# PIC16F887.net
KiCad netlist of a schematic drawn in Altium Designer
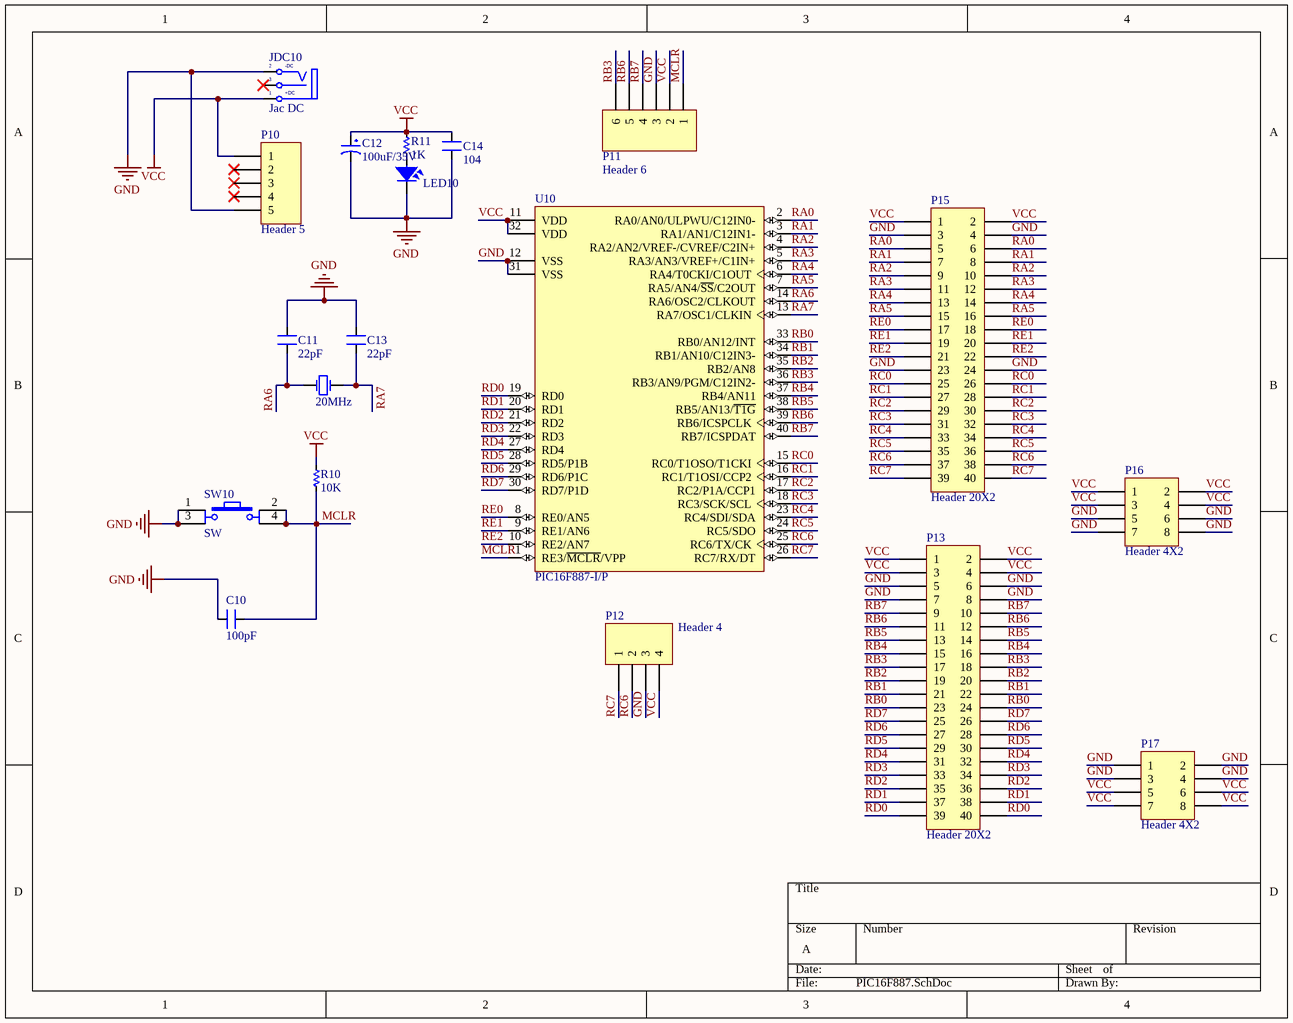
[diagram p0: PIC16F887.SchDoc]

(export (version "E")
  (design (tool "Eeschema 10.0.6"))
  (components
    (comp (ref "C10")
      (value "100pF")
      (footprint "CN1")
      (description "Cap np  1pF - 472pF")
      (libsource (lib "My Library") (part "CN1"))
    )
    (comp (ref "C11")
      (value "22pF")
      (footprint "CN1")
      (description "Cap np  1pF - 472pF")
      (libsource (lib "My Library") (part "CN1"))
    )
    (comp (ref "C12")
      (value "100uF/35V")
      (footprint "CP1.5/3.4")
      (description "Cap 100uF/35V - 470uF/16V")
      (libsource (lib "My Library") (part "CP3"))
    )
    (comp (ref "C13")
      (value "22pF")
      (footprint "CN1")
      (description "Cap np  1pF - 472pF")
      (libsource (lib "My Library") (part "CN1"))
    )
    (comp (ref "C14")
      (value "104")
      (footprint "CN1.5")
      (description "Cap np 682pF => 104pF")
      (libsource (lib "My Library") (part "CN1.5"))
    )
    (comp (ref "JDC10")
      (value "Jac DC")
      (footprint "DC-IN")
      (description "Jac DC input")
      (libsource (lib "My Library") (part "DCIN"))
    )
    (comp (ref "LED10")
      (value "LED")
      (footprint "LED-1206-Blue")
      (libsource (lib "My Library") (part "LED SMD"))
    )
    (comp (ref "P10")
      (value "Header 5")
      (footprint "HDR1X5")
      (description "Header, 5-Pin")
      (fields (field (name "PUBLISHER") "Altium Limited"))
      (libsource (lib "Miscellaneous Connectors") (part "Header 5"))
    )
    (comp (ref "P11")
      (value "Header 6")
      (footprint "HDR1X6")
      (description "Header, 6-Pin")
      (fields (field (name "PUBLISHER") "Altium Limited"))
      (libsource (lib "Miscellaneous Connectors") (part "Header 6"))
    )
    (comp (ref "P12")
      (value "Header 4")
      (footprint "HDR1X4")
      (description "Header, 4-Pin")
      (fields (field (name "PUBLISHER") "Altium Limited"))
      (libsource (lib "Miscellaneous Connectors") (part "Header 4"))
    )
    (comp (ref "P13")
      (value "Header 20X2")
      (footprint "HDR2X20")
      (description "Header, 20-Pin, Dual row")
      (fields (field (name "PUBLISHER") "Altium Limited"))
      (libsource (lib "Miscellaneous Connectors") (part "Header 20X2"))
    )
    (comp (ref "P15")
      (value "Header 20X2")
      (footprint "HDR2X20")
      (description "Header, 20-Pin, Dual row")
      (fields (field (name "PUBLISHER") "Altium Limited"))
      (libsource (lib "Miscellaneous Connectors") (part "Header 20X2"))
    )
    (comp (ref "P16")
      (value "Header 4X2")
      (footprint "HDR2X4")
      (description "Header, 4-Pin, Dual row")
      (fields (field (name "PUBLISHER") "Altium Limited"))
      (libsource (lib "Miscellaneous Connectors") (part "Header 4X2"))
    )
    (comp (ref "P17")
      (value "Header 4X2")
      (footprint "HDR2X4")
      (description "Header, 4-Pin, Dual row")
      (fields (field (name "PUBLISHER") "Altium Limited"))
      (libsource (lib "Miscellaneous Connectors") (part "Header 4X2"))
    )
    (comp (ref "R10")
      (value "10K")
      (footprint "RES-SMD-1206")
      (description "Resistor")
      (fields
        (field (name "MANUFACTURER") "Generic Components")
        (field (name "PUBLISHER") "Altium Hobart Technology Centre")
      )
      (libsource (lib "My Library") (part "Res-SMD"))
    )
    (comp (ref "R11")
      (value "1K")
      (footprint "RES-SMD-1206")
      (description "Resistor")
      (fields
        (field (name "MANUFACTURER") "Generic Components")
        (field (name "PUBLISHER") "Altium Hobart Technology Centre")
      )
      (libsource (lib "My Library") (part "Res-SMD"))
    )
    (comp (ref "SW10")
      (value "SW")
      (footprint "SW4")
      (description "Switch button 4 pin")
      (libsource (lib "My Library") (part "SW4"))
    )
    (comp (ref "U10")
      (value "PIC16F887-I/P")
      (footprint "PDIP600-P40")
      (fields (field (name "PUBLISHER") "Altium Limited"))
      (libsource (lib "Microchip Microcontroller 8-Bit PIC16") (part "PIC16F887-I/P"))
    )
    (comp (ref "Y10")
      (value "20MHz")
      (footprint "XTAL")
      (description "Crystal Oscillator")
      (fields (field (name "PUBLISHER") "Altium Limited"))
      (libsource (lib "My Library") (part "XTAL"))
    )
  )
  (nets
    (net (code "1") (name "/MCLR") (class "Default")
      (node (ref "C10") (pin "1") (pinfunction "1_1") (pintype "passive"))
      (node (ref "P11") (pin "1") (pinfunction "1_1") (pintype "passive"))
      (node (ref "R10") (pin "2") (pinfunction "2_2") (pintype "passive"))
      (node (ref "SW10") (pin "2") (pintype "passive"))
      (node (ref "SW10") (pin "4") (pintype "passive"))
      (node (ref "U10") (pin "1") (pinfunction "RE3/~{MCLR}/VPP_1") (pintype "bidirectional"))
    )
    (net (code "2") (name "/RA0") (class "Default")
      (node (ref "P15") (pin "5") (pinfunction "5_5") (pintype "passive"))
      (node (ref "P15") (pin "6") (pinfunction "6_6") (pintype "passive"))
      (node (ref "U10") (pin "2") (pinfunction "RA0/AN0/ULPWU/C12IN0-_2") (pintype "bidirectional"))
    )
    (net (code "3") (name "/RA1") (class "Default")
      (node (ref "P15") (pin "7") (pinfunction "7_7") (pintype "passive"))
      (node (ref "P15") (pin "8") (pinfunction "8_8") (pintype "passive"))
      (node (ref "U10") (pin "3") (pinfunction "RA1/AN1/C12IN1-_3") (pintype "bidirectional"))
    )
    (net (code "4") (name "/RA2") (class "Default")
      (node (ref "P15") (pin "10") (pinfunction "10_10") (pintype "passive"))
      (node (ref "P15") (pin "9") (pinfunction "9_9") (pintype "passive"))
      (node (ref "U10") (pin "4") (pinfunction "RA2/AN2/VREF-/CVREF/C2IN+_4") (pintype "bidirectional"))
    )
    (net (code "5") (name "/RA3") (class "Default")
      (node (ref "P15") (pin "11") (pinfunction "11_11") (pintype "passive"))
      (node (ref "P15") (pin "12") (pinfunction "12_12") (pintype "passive"))
      (node (ref "U10") (pin "5") (pinfunction "RA3/AN3/VREF+/C1IN+_5") (pintype "bidirectional"))
    )
    (net (code "6") (name "/RA4") (class "Default")
      (node (ref "P15") (pin "13") (pinfunction "13_13") (pintype "passive"))
      (node (ref "P15") (pin "14") (pinfunction "14_14") (pintype "passive"))
      (node (ref "U10") (pin "6") (pinfunction "RA4/T0CKI/C1OUT_6") (pintype "bidirectional"))
    )
    (net (code "7") (name "/RA5") (class "Default")
      (node (ref "P15") (pin "15") (pinfunction "15_15") (pintype "passive"))
      (node (ref "P15") (pin "16") (pinfunction "16_16") (pintype "passive"))
      (node (ref "U10") (pin "7") (pinfunction "RA5/AN4/~{SS}/C2OUT_7") (pintype "bidirectional"))
    )
    (net (code "8") (name "/RA6") (class "Default")
      (node (ref "C11") (pin "1") (pinfunction "1_1") (pintype "passive"))
      (node (ref "U10") (pin "14") (pinfunction "RA6/OSC2/CLKOUT_14") (pintype "bidirectional"))
      (node (ref "Y10") (pin "1") (pinfunction "OSC1_1") (pintype "passive"))
    )
    (net (code "9") (name "/RA7") (class "Default")
      (node (ref "C13") (pin "1") (pinfunction "1_1") (pintype "passive"))
      (node (ref "U10") (pin "13") (pinfunction "RA7/OSC1/CLKIN_13") (pintype "bidirectional"))
      (node (ref "Y10") (pin "2") (pinfunction "OSC2_2") (pintype "passive"))
    )
    (net (code "10") (name "/RB0") (class "Default")
      (node (ref "P13") (pin "23") (pinfunction "23_23") (pintype "passive"))
      (node (ref "P13") (pin "24") (pinfunction "24_24") (pintype "passive"))
      (node (ref "U10") (pin "33") (pinfunction "RB0/AN12/INT_33") (pintype "bidirectional"))
    )
    (net (code "11") (name "/RB1") (class "Default")
      (node (ref "P13") (pin "21") (pinfunction "21_21") (pintype "passive"))
      (node (ref "P13") (pin "22") (pinfunction "22_22") (pintype "passive"))
      (node (ref "U10") (pin "34") (pinfunction "RB1/AN10/C12IN3-_34") (pintype "bidirectional"))
    )
    (net (code "12") (name "/RB2") (class "Default")
      (node (ref "P13") (pin "19") (pinfunction "19_19") (pintype "passive"))
      (node (ref "P13") (pin "20") (pinfunction "20_20") (pintype "passive"))
      (node (ref "U10") (pin "35") (pinfunction "RB2/AN8_35") (pintype "bidirectional"))
    )
    (net (code "13") (name "/RB3") (class "Default")
      (node (ref "P11") (pin "6") (pinfunction "6_6") (pintype "passive"))
      (node (ref "P13") (pin "17") (pinfunction "17_17") (pintype "passive"))
      (node (ref "P13") (pin "18") (pinfunction "18_18") (pintype "passive"))
      (node (ref "U10") (pin "36") (pinfunction "RB3/AN9/PGM/C12IN2-_36") (pintype "bidirectional"))
    )
    (net (code "14") (name "/RB4") (class "Default")
      (node (ref "P13") (pin "15") (pinfunction "15_15") (pintype "passive"))
      (node (ref "P13") (pin "16") (pinfunction "16_16") (pintype "passive"))
      (node (ref "U10") (pin "37") (pinfunction "RB4/AN11_37") (pintype "bidirectional"))
    )
    (net (code "15") (name "/RB5") (class "Default")
      (node (ref "P13") (pin "13") (pinfunction "13_13") (pintype "passive"))
      (node (ref "P13") (pin "14") (pinfunction "14_14") (pintype "passive"))
      (node (ref "U10") (pin "38") (pinfunction "RB5/AN13/~{T1G}_38") (pintype "bidirectional"))
    )
    (net (code "16") (name "/RB6") (class "Default")
      (node (ref "P11") (pin "5") (pinfunction "5_5") (pintype "passive"))
      (node (ref "P13") (pin "11") (pinfunction "11_11") (pintype "passive"))
      (node (ref "P13") (pin "12") (pinfunction "12_12") (pintype "passive"))
      (node (ref "U10") (pin "39") (pinfunction "RB6/ICSPCLK_39") (pintype "bidirectional"))
    )
    (net (code "17") (name "/RB7") (class "Default")
      (node (ref "P11") (pin "4") (pinfunction "4_4") (pintype "passive"))
      (node (ref "P13") (pin "10") (pinfunction "10_10") (pintype "passive"))
      (node (ref "P13") (pin "9") (pinfunction "9_9") (pintype "passive"))
      (node (ref "U10") (pin "40") (pinfunction "RB7/ICSPDAT_40") (pintype "bidirectional"))
    )
    (net (code "18") (name "/RC0") (class "Default")
      (node (ref "P15") (pin "25") (pinfunction "25_25") (pintype "passive"))
      (node (ref "P15") (pin "26") (pinfunction "26_26") (pintype "passive"))
      (node (ref "U10") (pin "15") (pinfunction "RC0/T1OSO/T1CKI_15") (pintype "bidirectional"))
    )
    (net (code "19") (name "/RC1") (class "Default")
      (node (ref "P15") (pin "27") (pinfunction "27_27") (pintype "passive"))
      (node (ref "P15") (pin "28") (pinfunction "28_28") (pintype "passive"))
      (node (ref "U10") (pin "16") (pinfunction "RC1/T1OSI/CCP2_16") (pintype "bidirectional"))
    )
    (net (code "20") (name "/RC2") (class "Default")
      (node (ref "P15") (pin "29") (pinfunction "29_29") (pintype "passive"))
      (node (ref "P15") (pin "30") (pinfunction "30_30") (pintype "passive"))
      (node (ref "U10") (pin "17") (pinfunction "RC2/P1A/CCP1_17") (pintype "bidirectional"))
    )
    (net (code "21") (name "/RC3") (class "Default")
      (node (ref "P15") (pin "31") (pinfunction "31_31") (pintype "passive"))
      (node (ref "P15") (pin "32") (pinfunction "32_32") (pintype "passive"))
      (node (ref "U10") (pin "18") (pinfunction "RC3/SCK/SCL_18") (pintype "bidirectional"))
    )
    (net (code "22") (name "/RC4") (class "Default")
      (node (ref "P15") (pin "33") (pinfunction "33_33") (pintype "passive"))
      (node (ref "P15") (pin "34") (pinfunction "34_34") (pintype "passive"))
      (node (ref "U10") (pin "23") (pinfunction "RC4/SDI/SDA_23") (pintype "bidirectional"))
    )
    (net (code "23") (name "/RC5") (class "Default")
      (node (ref "P15") (pin "35") (pinfunction "35_35") (pintype "passive"))
      (node (ref "P15") (pin "36") (pinfunction "36_36") (pintype "passive"))
      (node (ref "U10") (pin "24") (pinfunction "RC5/SDO_24") (pintype "bidirectional"))
    )
    (net (code "24") (name "/RC6") (class "Default")
      (node (ref "P12") (pin "2") (pinfunction "2_2") (pintype "passive"))
      (node (ref "P15") (pin "37") (pinfunction "37_37") (pintype "passive"))
      (node (ref "P15") (pin "38") (pinfunction "38_38") (pintype "passive"))
      (node (ref "U10") (pin "25") (pinfunction "RC6/TX/CK_25") (pintype "bidirectional"))
    )
    (net (code "25") (name "/RC7") (class "Default")
      (node (ref "P12") (pin "1") (pinfunction "1_1") (pintype "passive"))
      (node (ref "P15") (pin "39") (pinfunction "39_39") (pintype "passive"))
      (node (ref "P15") (pin "40") (pinfunction "40_40") (pintype "passive"))
      (node (ref "U10") (pin "26") (pinfunction "RC7/RX/DT_26") (pintype "bidirectional"))
    )
    (net (code "26") (name "/RD0") (class "Default")
      (node (ref "P13") (pin "39") (pinfunction "39_39") (pintype "passive"))
      (node (ref "P13") (pin "40") (pinfunction "40_40") (pintype "passive"))
      (node (ref "U10") (pin "19") (pinfunction "RD0_19") (pintype "bidirectional"))
    )
    (net (code "27") (name "/RD1") (class "Default")
      (node (ref "P13") (pin "37") (pinfunction "37_37") (pintype "passive"))
      (node (ref "P13") (pin "38") (pinfunction "38_38") (pintype "passive"))
      (node (ref "U10") (pin "20") (pinfunction "RD1_20") (pintype "bidirectional"))
    )
    (net (code "28") (name "/RD2") (class "Default")
      (node (ref "P13") (pin "35") (pinfunction "35_35") (pintype "passive"))
      (node (ref "P13") (pin "36") (pinfunction "36_36") (pintype "passive"))
      (node (ref "U10") (pin "21") (pinfunction "RD2_21") (pintype "bidirectional"))
    )
    (net (code "29") (name "/RD3") (class "Default")
      (node (ref "P13") (pin "33") (pinfunction "33_33") (pintype "passive"))
      (node (ref "P13") (pin "34") (pinfunction "34_34") (pintype "passive"))
      (node (ref "U10") (pin "22") (pinfunction "RD3_22") (pintype "bidirectional"))
    )
    (net (code "30") (name "/RD4") (class "Default")
      (node (ref "P13") (pin "31") (pinfunction "31_31") (pintype "passive"))
      (node (ref "P13") (pin "32") (pinfunction "32_32") (pintype "passive"))
      (node (ref "U10") (pin "27") (pinfunction "RD4_27") (pintype "bidirectional"))
    )
    (net (code "31") (name "/RD5") (class "Default")
      (node (ref "P13") (pin "29") (pinfunction "29_29") (pintype "passive"))
      (node (ref "P13") (pin "30") (pinfunction "30_30") (pintype "passive"))
      (node (ref "U10") (pin "28") (pinfunction "RD5/P1B_28") (pintype "bidirectional"))
    )
    (net (code "32") (name "/RD6") (class "Default")
      (node (ref "P13") (pin "27") (pinfunction "27_27") (pintype "passive"))
      (node (ref "P13") (pin "28") (pinfunction "28_28") (pintype "passive"))
      (node (ref "U10") (pin "29") (pinfunction "RD6/P1C_29") (pintype "bidirectional"))
    )
    (net (code "33") (name "/RD7") (class "Default")
      (node (ref "P13") (pin "25") (pinfunction "25_25") (pintype "passive"))
      (node (ref "P13") (pin "26") (pinfunction "26_26") (pintype "passive"))
      (node (ref "U10") (pin "30") (pinfunction "RD7/P1D_30") (pintype "bidirectional"))
    )
    (net (code "34") (name "/RE0") (class "Default")
      (node (ref "P15") (pin "17") (pinfunction "17_17") (pintype "passive"))
      (node (ref "P15") (pin "18") (pinfunction "18_18") (pintype "passive"))
      (node (ref "U10") (pin "8") (pinfunction "RE0/AN5_8") (pintype "bidirectional"))
    )
    (net (code "35") (name "/RE1") (class "Default")
      (node (ref "P15") (pin "19") (pinfunction "19_19") (pintype "passive"))
      (node (ref "P15") (pin "20") (pinfunction "20_20") (pintype "passive"))
      (node (ref "U10") (pin "9") (pinfunction "RE1/AN6_9") (pintype "bidirectional"))
    )
    (net (code "36") (name "/RE2") (class "Default")
      (node (ref "P15") (pin "21") (pinfunction "21_21") (pintype "passive"))
      (node (ref "P15") (pin "22") (pinfunction "22_22") (pintype "passive"))
      (node (ref "U10") (pin "10") (pinfunction "RE2/AN7_10") (pintype "bidirectional"))
    )
    (net (code "37") (name "GND") (class "Default")
      (node (ref "C10") (pin "2") (pinfunction "2_2") (pintype "passive"))
      (node (ref "C11") (pin "2") (pinfunction "2_2") (pintype "passive"))
      (node (ref "C12") (pin "2") (pinfunction "2_2") (pintype "passive"))
      (node (ref "C13") (pin "2") (pinfunction "2_2") (pintype "passive"))
      (node (ref "C14") (pin "1") (pinfunction "1_1") (pintype "passive"))
      (node (ref "JDC10") (pin "2") (pinfunction "TN_2") (pintype "passive"))
      (node (ref "LED10") (pin "2") (pinfunction "2_2") (pintype "passive"))
      (node (ref "P10") (pin "5") (pinfunction "5_5") (pintype "passive"))
      (node (ref "P11") (pin "3") (pinfunction "3_3") (pintype "passive"))
      (node (ref "P12") (pin "3") (pinfunction "3_3") (pintype "passive"))
      (node (ref "P13") (pin "5") (pinfunction "5_5") (pintype "passive"))
      (node (ref "P13") (pin "6") (pinfunction "6_6") (pintype "passive"))
      (node (ref "P13") (pin "7") (pinfunction "7_7") (pintype "passive"))
      (node (ref "P13") (pin "8") (pinfunction "8_8") (pintype "passive"))
      (node (ref "P15") (pin "23") (pinfunction "23_23") (pintype "passive"))
      (node (ref "P15") (pin "24") (pinfunction "24_24") (pintype "passive"))
      (node (ref "P15") (pin "3") (pinfunction "3_3") (pintype "passive"))
      (node (ref "P15") (pin "4") (pinfunction "4_4") (pintype "passive"))
      (node (ref "P16") (pin "5") (pinfunction "5_5") (pintype "passive"))
      (node (ref "P16") (pin "6") (pinfunction "6_6") (pintype "passive"))
      (node (ref "P16") (pin "7") (pinfunction "7_7") (pintype "passive"))
      (node (ref "P16") (pin "8") (pinfunction "8_8") (pintype "passive"))
      (node (ref "P17") (pin "1") (pinfunction "1_1") (pintype "passive"))
      (node (ref "P17") (pin "2") (pinfunction "2_2") (pintype "passive"))
      (node (ref "P17") (pin "3") (pinfunction "3_3") (pintype "passive"))
      (node (ref "P17") (pin "4") (pinfunction "4_4") (pintype "passive"))
      (node (ref "SW10") (pin "1") (pintype "passive"))
      (node (ref "SW10") (pin "3") (pintype "passive"))
      (node (ref "U10") (pin "12") (pinfunction "VSS_12") (pintype "power_in"))
      (node (ref "U10") (pin "31") (pinfunction "VSS_31") (pintype "power_in"))
    )
    (net (code "38") (name "Net-(LED10-Pad1)") (class "Default")
      (node (ref "LED10") (pin "1") (pinfunction "1_1") (pintype "passive"))
      (node (ref "R11") (pin "2") (pinfunction "2_2") (pintype "passive"))
    )
    (net (code "39") (name "VCC") (class "Default")
      (node (ref "C12") (pin "1") (pinfunction "1_1") (pintype "passive"))
      (node (ref "C14") (pin "2") (pinfunction "2_2") (pintype "passive"))
      (node (ref "JDC10") (pin "1") (pinfunction "T_1") (pintype "passive"))
      (node (ref "P10") (pin "1") (pinfunction "1_1") (pintype "passive"))
      (node (ref "P11") (pin "2") (pinfunction "2_2") (pintype "passive"))
      (node (ref "P12") (pin "4") (pinfunction "4_4") (pintype "passive"))
      (node (ref "P13") (pin "1") (pinfunction "1_1") (pintype "passive"))
      (node (ref "P13") (pin "2") (pinfunction "2_2") (pintype "passive"))
      (node (ref "P13") (pin "3") (pinfunction "3_3") (pintype "passive"))
      (node (ref "P13") (pin "4") (pinfunction "4_4") (pintype "passive"))
      (node (ref "P15") (pin "1") (pinfunction "1_1") (pintype "passive"))
      (node (ref "P15") (pin "2") (pinfunction "2_2") (pintype "passive"))
      (node (ref "P16") (pin "1") (pinfunction "1_1") (pintype "passive"))
      (node (ref "P16") (pin "2") (pinfunction "2_2") (pintype "passive"))
      (node (ref "P16") (pin "3") (pinfunction "3_3") (pintype "passive"))
      (node (ref "P16") (pin "4") (pinfunction "4_4") (pintype "passive"))
      (node (ref "P17") (pin "5") (pinfunction "5_5") (pintype "passive"))
      (node (ref "P17") (pin "6") (pinfunction "6_6") (pintype "passive"))
      (node (ref "P17") (pin "7") (pinfunction "7_7") (pintype "passive"))
      (node (ref "P17") (pin "8") (pinfunction "8_8") (pintype "passive"))
      (node (ref "R10") (pin "1") (pinfunction "1_1") (pintype "passive"))
      (node (ref "R11") (pin "1") (pinfunction "1_1") (pintype "passive"))
      (node (ref "U10") (pin "11") (pinfunction "VDD_11") (pintype "power_in"))
      (node (ref "U10") (pin "32") (pinfunction "VDD_32") (pintype "power_in"))
    )
    (net (code "40") (name "unconnected-(JDC10-S-Pad3)") (class "Default")
      (node (ref "JDC10") (pin "3") (pinfunction "S_3") (pintype "power_in+no_connect"))
    )
    (net (code "41") (name "unconnected-(P10-Pad2)") (class "Default")
      (node (ref "P10") (pin "2") (pinfunction "2_2") (pintype "passive+no_connect"))
    )
    (net (code "42") (name "unconnected-(P10-Pad3)") (class "Default")
      (node (ref "P10") (pin "3") (pinfunction "3_3") (pintype "passive+no_connect"))
    )
    (net (code "43") (name "unconnected-(P10-Pad4)") (class "Default")
      (node (ref "P10") (pin "4") (pinfunction "4_4") (pintype "passive+no_connect"))
    )
  )
)
